# punchdriver.net
KiCad netlist of a schematic drawn in EAGLE
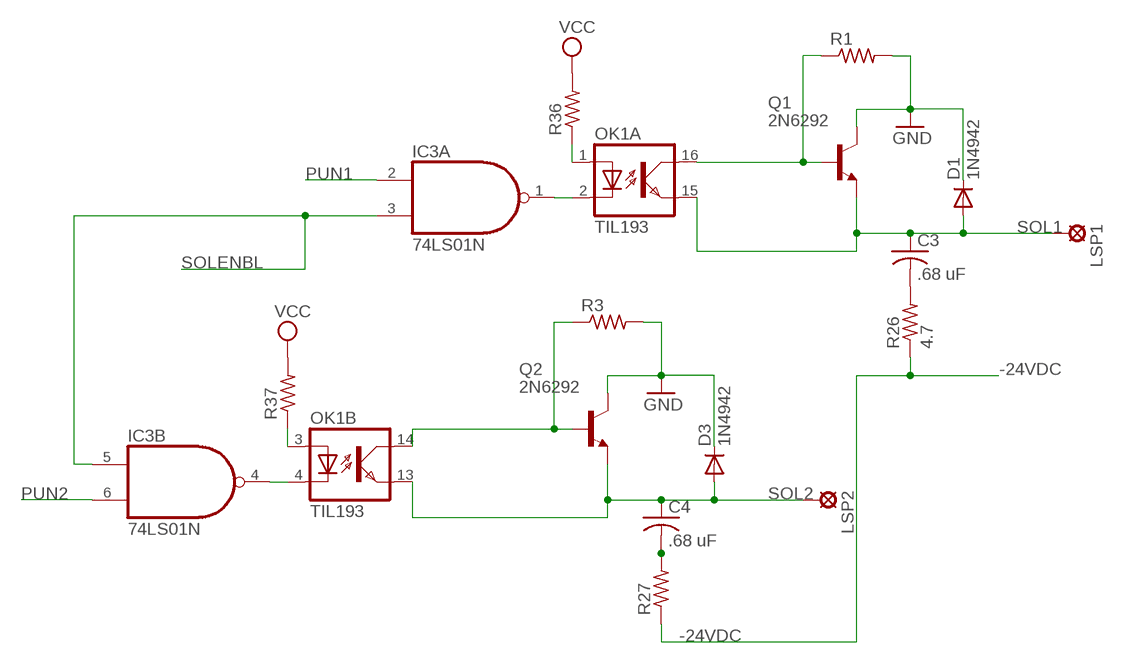
[diagram p0: schematic, sheet 1]
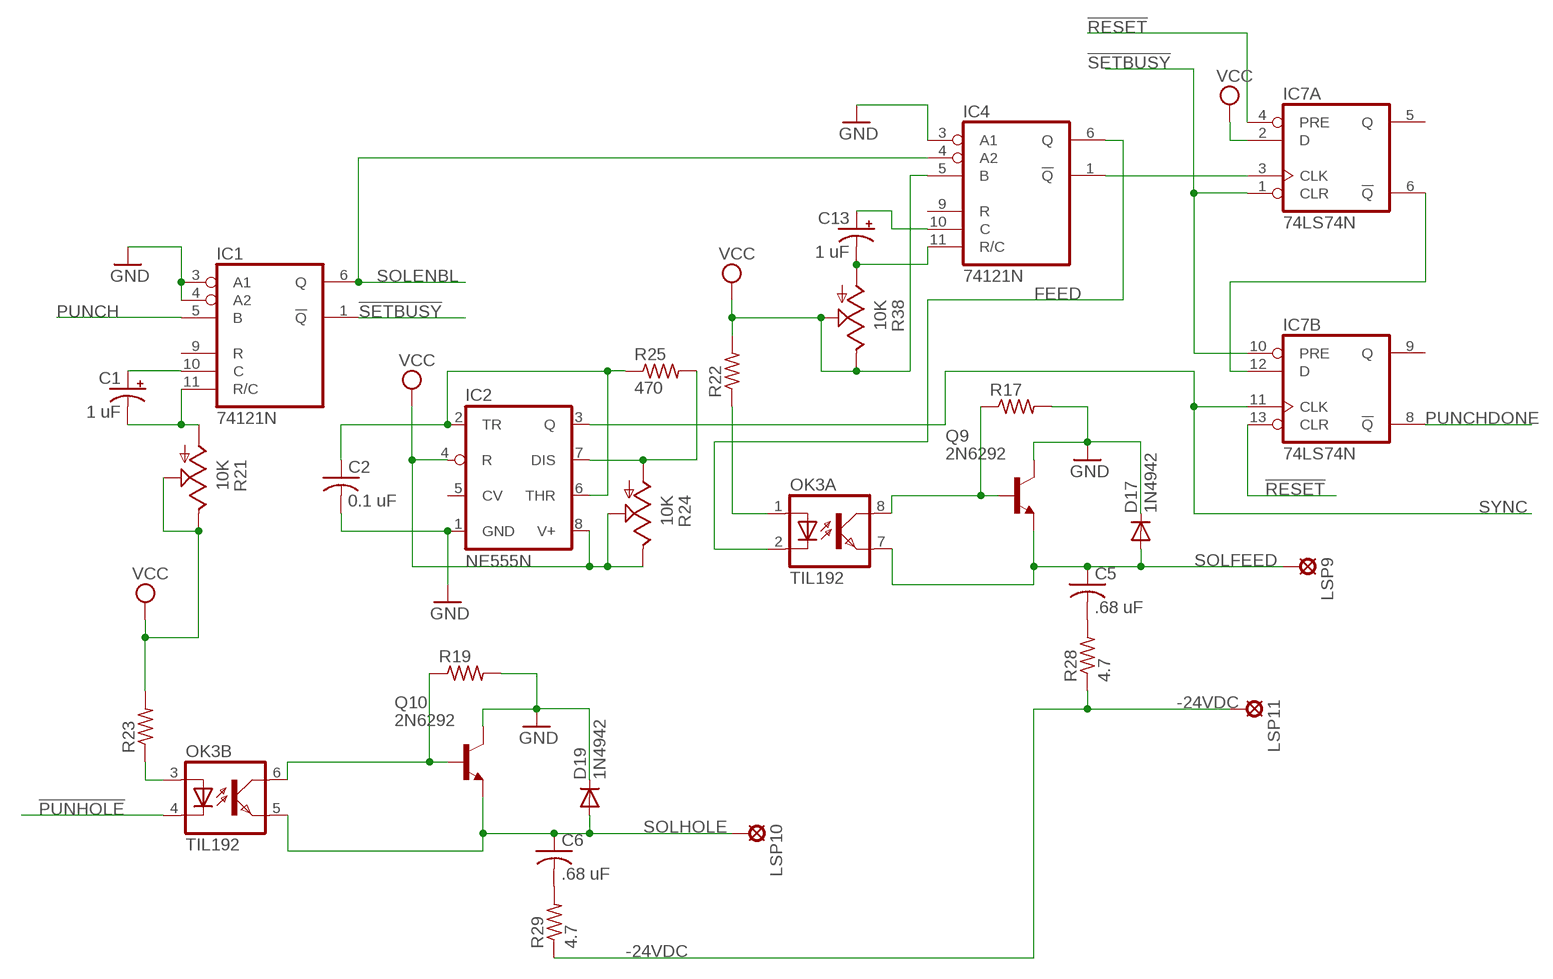
[diagram p1: schematic, sheet 2]
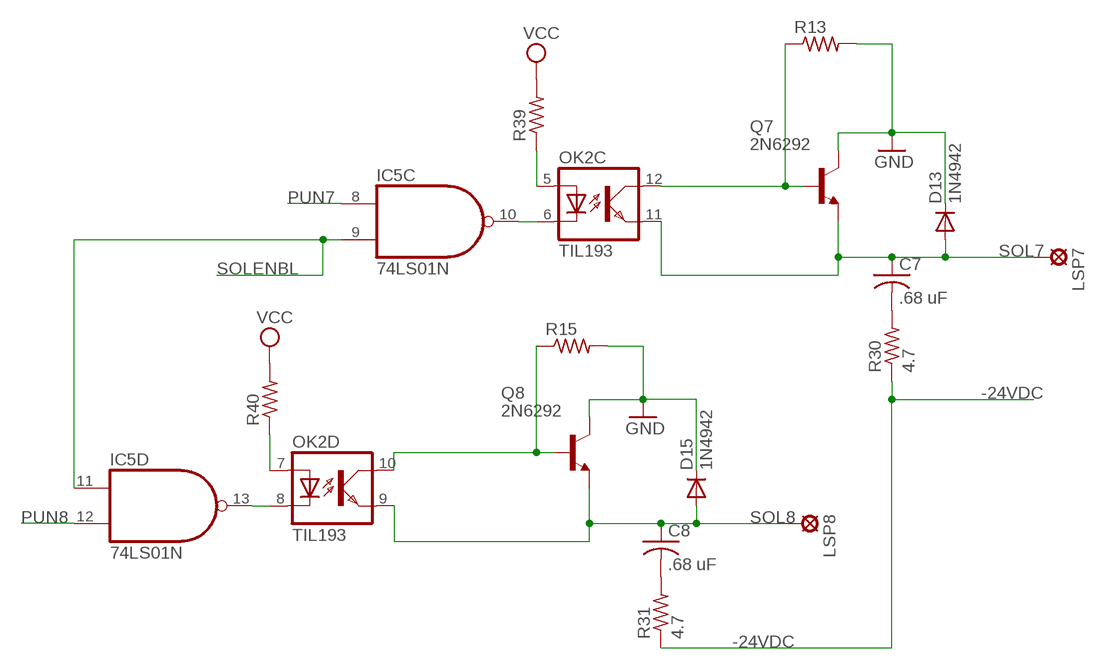
[diagram p2: schematic, sheet 3]
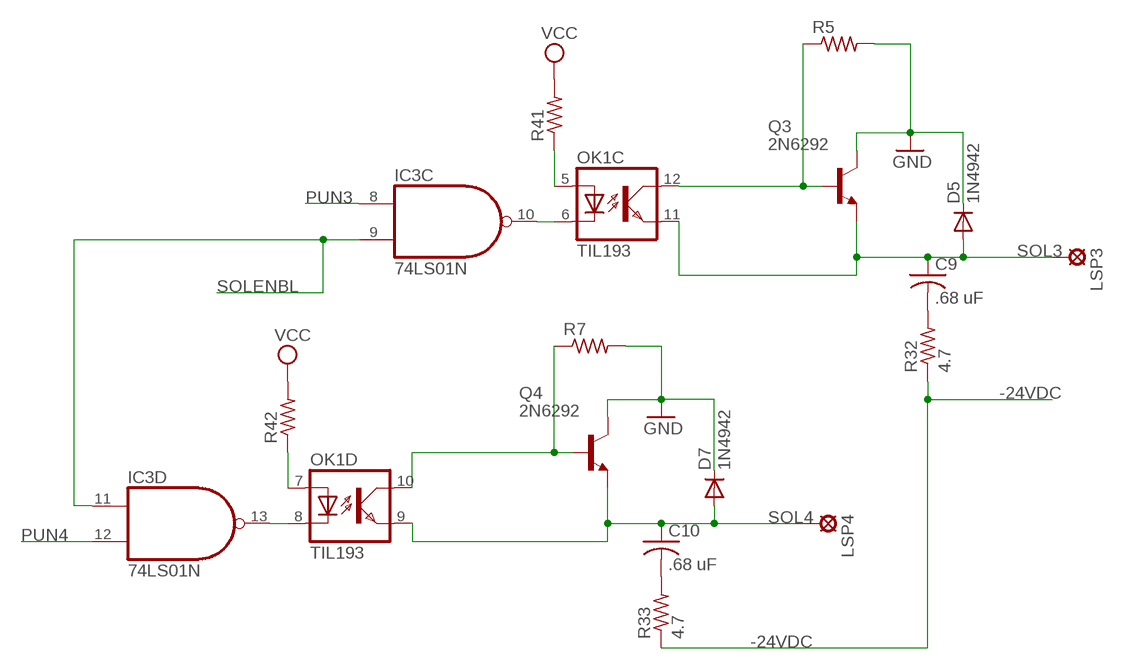
[diagram p3: schematic, sheet 4]
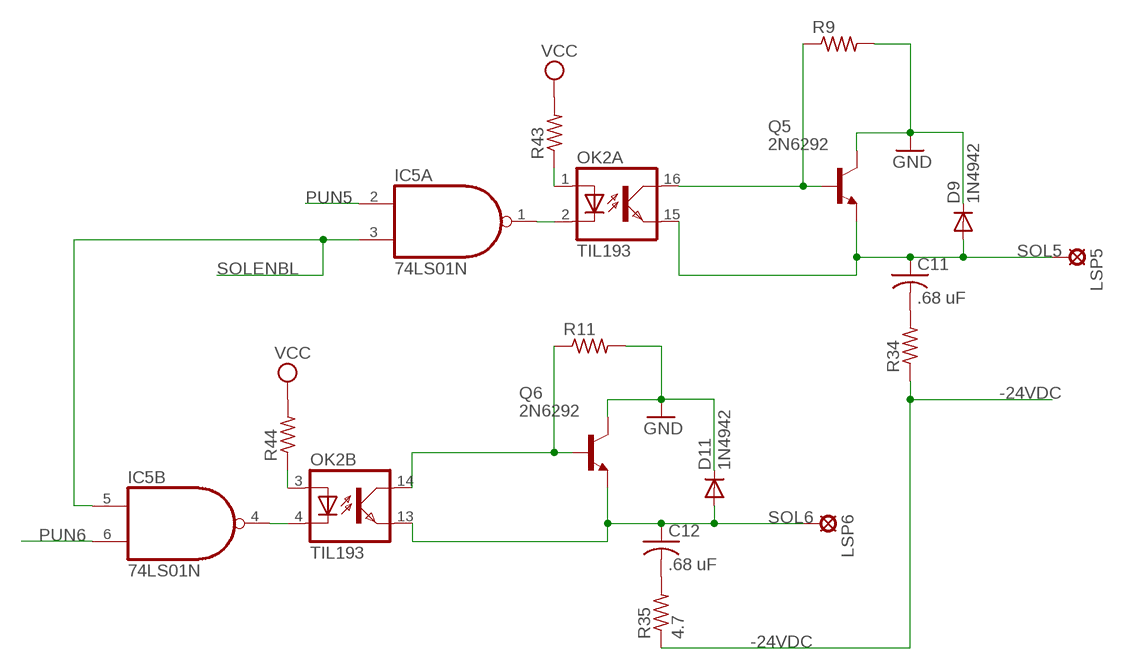
[diagram p4: schematic, sheet 5]
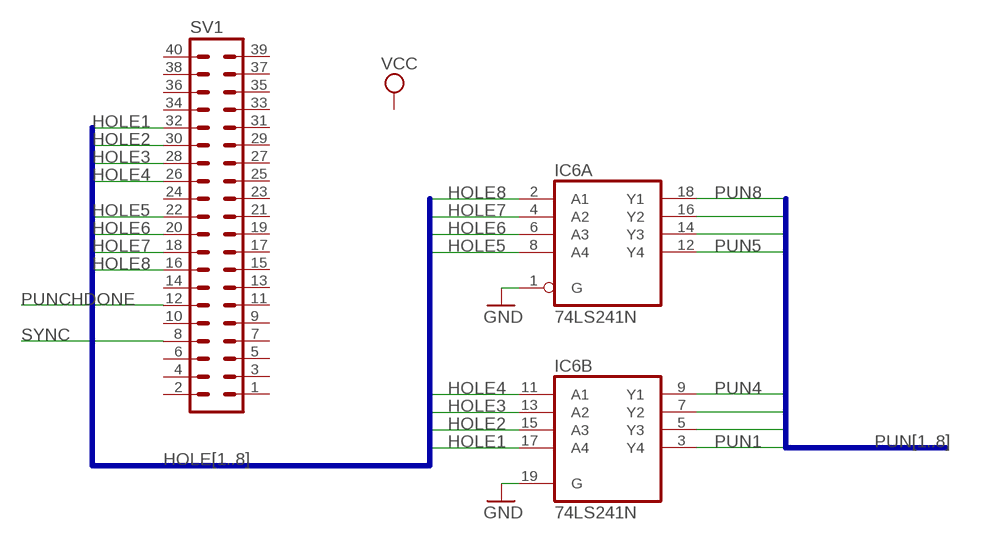
[diagram p5: schematic, sheet 6]

(export (version "E")
  (design (tool "Eeschema 10.0.6"))
  (components
    (comp (ref "IC6")
      (value "74LS241N")
      (footprint "eagle-import:DIL20")
      (libsource (lib "eagle-import") (part "74241NLS"))
    )
    (comp (ref "SV1")
      (value "MA20-2")
      (footprint "eagle-import:MA20-2")
      (libsource (lib "eagle-import") (part "MA20-2"))
    )
    (comp (ref "C1")
      (value "1 uF")
      (footprint "eagle-import:B45181A")
      (libsource (lib "eagle-import") (part "CPOL-USB45181A"))
    )
    (comp (ref "C2")
      (value "0.1 uF")
      (footprint "eagle-import:C050-025X075")
      (libsource (lib "eagle-import") (part "C-US050-025X075"))
    )
    (comp (ref "C5")
      (value ".68 uF")
      (footprint "eagle-import:C050-025X075")
      (libsource (lib "eagle-import") (part "C-US050-025X075"))
    )
    (comp (ref "C6")
      (value ".68 uF")
      (footprint "eagle-import:C050-025X075")
      (libsource (lib "eagle-import") (part "C-US050-025X075"))
    )
    (comp (ref "C13")
      (value "1 uF")
      (footprint "eagle-import:B45181A")
      (libsource (lib "eagle-import") (part "CPOL-USB45181A"))
    )
    (comp (ref "D17")
      (value "1N4942")
      (footprint "eagle-import:DO41-10")
      (libsource (lib "eagle-import") (part "1N4942"))
    )
    (comp (ref "D19")
      (value "1N4942")
      (footprint "eagle-import:DO41-10")
      (libsource (lib "eagle-import") (part "1N4942"))
    )
    (comp (ref "IC1")
      (value "74121N")
      (footprint "eagle-import:DIL14")
      (libsource (lib "eagle-import") (part "74121N"))
    )
    (comp (ref "IC2")
      (value "NE555N")
      (footprint "eagle-import:DIL08")
      (libsource (lib "eagle-import") (part "555NNE"))
    )
    (comp (ref "IC4")
      (value "74121N")
      (footprint "eagle-import:DIL14")
      (libsource (lib "eagle-import") (part "74121N"))
    )
    (comp (ref "IC7")
      (value "74LS74N")
      (footprint "eagle-import:DIL14")
      (libsource (lib "eagle-import") (part "7474NLS"))
    )
    (comp (ref "LSP9")
      (value "SE13")
      (footprint "eagle-import:SE13")
      (libsource (lib "eagle-import") (part "SE13"))
    )
    (comp (ref "LSP10")
      (value "SE13")
      (footprint "eagle-import:SE13")
      (libsource (lib "eagle-import") (part "SE13"))
    )
    (comp (ref "LSP11")
      (value "SE13")
      (footprint "eagle-import:SE13")
      (libsource (lib "eagle-import") (part "SE13"))
    )
    (comp (ref "OK3")
      (value "TIL192")
      (footprint "eagle-import:DIL08")
      (libsource (lib "eagle-import") (part "TIL192"))
    )
    (comp (ref "Q9")
      (value "2N6292")
      (footprint "eagle-import:TO220")
      (libsource (lib "eagle-import") (part "2N6292"))
    )
    (comp (ref "Q10")
      (value "2N6292")
      (footprint "eagle-import:TO220")
      (libsource (lib "eagle-import") (part "2N6292"))
    )
    (comp (ref "R17")
      (value "R-US_0207/10")
      (footprint "eagle-import:0207_10")
      (libsource (lib "eagle-import") (part "R-US_0207/10"))
    )
    (comp (ref "R19")
      (value "R-US_0207/10")
      (footprint "eagle-import:0207_10")
      (libsource (lib "eagle-import") (part "R-US_0207/10"))
    )
    (comp (ref "R21")
      (value "10K")
      (footprint "eagle-import:PT-SPIN")
      (libsource (lib "eagle-import") (part "TRIM_US-PTSPIN"))
    )
    (comp (ref "R22")
      (value "R-US_0207/10")
      (footprint "eagle-import:0207_10")
      (libsource (lib "eagle-import") (part "R-US_0207/10"))
    )
    (comp (ref "R23")
      (value "R-US_0207/10")
      (footprint "eagle-import:0207_10")
      (libsource (lib "eagle-import") (part "R-US_0207/10"))
    )
    (comp (ref "R24")
      (value "10K")
      (footprint "eagle-import:PT-SPIN")
      (libsource (lib "eagle-import") (part "TRIM_US-PTSPIN"))
    )
    (comp (ref "R25")
      (value "470")
      (footprint "eagle-import:0207_10")
      (libsource (lib "eagle-import") (part "R-US_0207/10"))
    )
    (comp (ref "R28")
      (value "4.7")
      (footprint "eagle-import:0207_10")
      (libsource (lib "eagle-import") (part "R-US_0207/10"))
    )
    (comp (ref "R29")
      (value "4.7")
      (footprint "eagle-import:0207_10")
      (libsource (lib "eagle-import") (part "R-US_0207/10"))
    )
    (comp (ref "R38")
      (value "10K")
      (footprint "eagle-import:PT-SPIN")
      (libsource (lib "eagle-import") (part "TRIM_US-PTSPIN"))
    )
    (comp (ref "C3")
      (value ".68 uF")
      (footprint "eagle-import:C050-025X075")
      (libsource (lib "eagle-import") (part "C-US050-025X075"))
    )
    (comp (ref "C4")
      (value ".68 uF")
      (footprint "eagle-import:C050-025X075")
      (libsource (lib "eagle-import") (part "C-US050-025X075"))
    )
    (comp (ref "D1")
      (value "1N4942")
      (footprint "eagle-import:DO41-10")
      (libsource (lib "eagle-import") (part "1N4942"))
    )
    (comp (ref "D3")
      (value "1N4942")
      (footprint "eagle-import:DO41-10")
      (libsource (lib "eagle-import") (part "1N4942"))
    )
    (comp (ref "IC3")
      (value "74LS01N")
      (footprint "eagle-import:DIL14")
      (libsource (lib "eagle-import") (part "7401NLS"))
    )
    (comp (ref "LSP1")
      (value "SE13")
      (footprint "eagle-import:SE13")
      (libsource (lib "eagle-import") (part "SE13"))
    )
    (comp (ref "LSP2")
      (value "SE13")
      (footprint "eagle-import:SE13")
      (libsource (lib "eagle-import") (part "SE13"))
    )
    (comp (ref "OK1")
      (value "TIL193")
      (footprint "eagle-import:DIL16")
      (libsource (lib "eagle-import") (part "TIL193"))
    )
    (comp (ref "Q1")
      (value "2N6292")
      (footprint "eagle-import:TO220")
      (libsource (lib "eagle-import") (part "2N6292"))
    )
    (comp (ref "Q2")
      (value "2N6292")
      (footprint "eagle-import:TO220")
      (libsource (lib "eagle-import") (part "2N6292"))
    )
    (comp (ref "R1")
      (value "R-US_0207/10")
      (footprint "eagle-import:0207_10")
      (libsource (lib "eagle-import") (part "R-US_0207/10"))
    )
    (comp (ref "R3")
      (value "R-US_0207/10")
      (footprint "eagle-import:0207_10")
      (libsource (lib "eagle-import") (part "R-US_0207/10"))
    )
    (comp (ref "R26")
      (value "4.7")
      (footprint "eagle-import:0207_10")
      (libsource (lib "eagle-import") (part "R-US_0207/10"))
    )
    (comp (ref "R27")
      (value "R-US_0207/10")
      (footprint "eagle-import:0207_10")
      (libsource (lib "eagle-import") (part "R-US_0207/10"))
    )
    (comp (ref "R36")
      (value "R-US_0207/10")
      (footprint "eagle-import:0207_10")
      (libsource (lib "eagle-import") (part "R-US_0207/10"))
    )
    (comp (ref "R37")
      (value "R-US_0207/10")
      (footprint "eagle-import:0207_10")
      (libsource (lib "eagle-import") (part "R-US_0207/10"))
    )
    (comp (ref "C7")
      (value ".68 uF")
      (footprint "eagle-import:C050-025X075")
      (libsource (lib "eagle-import") (part "C-US050-025X075"))
    )
    (comp (ref "C8")
      (value ".68 uF")
      (footprint "eagle-import:C050-025X075")
      (libsource (lib "eagle-import") (part "C-US050-025X075"))
    )
    (comp (ref "D13")
      (value "1N4942")
      (footprint "eagle-import:DO41-10")
      (libsource (lib "eagle-import") (part "1N4942"))
    )
    (comp (ref "D15")
      (value "1N4942")
      (footprint "eagle-import:DO41-10")
      (libsource (lib "eagle-import") (part "1N4942"))
    )
    (comp (ref "IC5")
      (value "74LS01N")
      (footprint "eagle-import:DIL14")
      (libsource (lib "eagle-import") (part "7401NLS"))
    )
    (comp (ref "LSP7")
      (value "SE13")
      (footprint "eagle-import:SE13")
      (libsource (lib "eagle-import") (part "SE13"))
    )
    (comp (ref "LSP8")
      (value "SE13")
      (footprint "eagle-import:SE13")
      (libsource (lib "eagle-import") (part "SE13"))
    )
    (comp (ref "OK2")
      (value "TIL193")
      (footprint "eagle-import:DIL16")
      (libsource (lib "eagle-import") (part "TIL193"))
    )
    (comp (ref "Q7")
      (value "2N6292")
      (footprint "eagle-import:TO220")
      (libsource (lib "eagle-import") (part "2N6292"))
    )
    (comp (ref "Q8")
      (value "2N6292")
      (footprint "eagle-import:TO220")
      (libsource (lib "eagle-import") (part "2N6292"))
    )
    (comp (ref "R13")
      (value "R-US_0207/10")
      (footprint "eagle-import:0207_10")
      (libsource (lib "eagle-import") (part "R-US_0207/10"))
    )
    (comp (ref "R15")
      (value "R-US_0207/10")
      (footprint "eagle-import:0207_10")
      (libsource (lib "eagle-import") (part "R-US_0207/10"))
    )
    (comp (ref "R30")
      (value "4.7")
      (footprint "eagle-import:0207_10")
      (libsource (lib "eagle-import") (part "R-US_0207/10"))
    )
    (comp (ref "R31")
      (value "4.7")
      (footprint "eagle-import:0207_10")
      (libsource (lib "eagle-import") (part "R-US_0207/10"))
    )
    (comp (ref "R39")
      (value "R-US_0207/10")
      (footprint "eagle-import:0207_10")
      (libsource (lib "eagle-import") (part "R-US_0207/10"))
    )
    (comp (ref "R40")
      (value "R-US_0207/10")
      (footprint "eagle-import:0207_10")
      (libsource (lib "eagle-import") (part "R-US_0207/10"))
    )
    (comp (ref "C9")
      (value ".68 uF")
      (footprint "eagle-import:C050-025X075")
      (libsource (lib "eagle-import") (part "C-US050-025X075"))
    )
    (comp (ref "C10")
      (value ".68 uF")
      (footprint "eagle-import:C050-025X075")
      (libsource (lib "eagle-import") (part "C-US050-025X075"))
    )
    (comp (ref "D5")
      (value "1N4942")
      (footprint "eagle-import:DO41-10")
      (libsource (lib "eagle-import") (part "1N4942"))
    )
    (comp (ref "D7")
      (value "1N4942")
      (footprint "eagle-import:DO41-10")
      (libsource (lib "eagle-import") (part "1N4942"))
    )
    (comp (ref "LSP3")
      (value "SE13")
      (footprint "eagle-import:SE13")
      (libsource (lib "eagle-import") (part "SE13"))
    )
    (comp (ref "LSP4")
      (value "SE13")
      (footprint "eagle-import:SE13")
      (libsource (lib "eagle-import") (part "SE13"))
    )
    (comp (ref "Q3")
      (value "2N6292")
      (footprint "eagle-import:TO220")
      (libsource (lib "eagle-import") (part "2N6292"))
    )
    (comp (ref "Q4")
      (value "2N6292")
      (footprint "eagle-import:TO220")
      (libsource (lib "eagle-import") (part "2N6292"))
    )
    (comp (ref "R5")
      (value "R-US_0207/10")
      (footprint "eagle-import:0207_10")
      (libsource (lib "eagle-import") (part "R-US_0207/10"))
    )
    (comp (ref "R7")
      (value "R-US_0207/10")
      (footprint "eagle-import:0207_10")
      (libsource (lib "eagle-import") (part "R-US_0207/10"))
    )
    (comp (ref "R32")
      (value "4.7")
      (footprint "eagle-import:0207_10")
      (libsource (lib "eagle-import") (part "R-US_0207/10"))
    )
    (comp (ref "R33")
      (value "4.7")
      (footprint "eagle-import:0207_10")
      (libsource (lib "eagle-import") (part "R-US_0207/10"))
    )
    (comp (ref "R41")
      (value "R-US_0207/10")
      (footprint "eagle-import:0207_10")
      (libsource (lib "eagle-import") (part "R-US_0207/10"))
    )
    (comp (ref "R42")
      (value "R-US_0207/10")
      (footprint "eagle-import:0207_10")
      (libsource (lib "eagle-import") (part "R-US_0207/10"))
    )
    (comp (ref "C11")
      (value ".68 uF")
      (footprint "eagle-import:C050-025X075")
      (libsource (lib "eagle-import") (part "C-US050-025X075"))
    )
    (comp (ref "C12")
      (value ".68 uF")
      (footprint "eagle-import:C050-025X075")
      (libsource (lib "eagle-import") (part "C-US050-025X075"))
    )
    (comp (ref "D9")
      (value "1N4942")
      (footprint "eagle-import:DO41-10")
      (libsource (lib "eagle-import") (part "1N4942"))
    )
    (comp (ref "D11")
      (value "1N4942")
      (footprint "eagle-import:DO41-10")
      (libsource (lib "eagle-import") (part "1N4942"))
    )
    (comp (ref "LSP5")
      (value "SE13")
      (footprint "eagle-import:SE13")
      (libsource (lib "eagle-import") (part "SE13"))
    )
    (comp (ref "LSP6")
      (value "SE13")
      (footprint "eagle-import:SE13")
      (libsource (lib "eagle-import") (part "SE13"))
    )
    (comp (ref "Q5")
      (value "2N6292")
      (footprint "eagle-import:TO220")
      (libsource (lib "eagle-import") (part "2N6292"))
    )
    (comp (ref "Q6")
      (value "2N6292")
      (footprint "eagle-import:TO220")
      (libsource (lib "eagle-import") (part "2N6292"))
    )
    (comp (ref "R9")
      (value "R-US_0207/10")
      (footprint "eagle-import:0207_10")
      (libsource (lib "eagle-import") (part "R-US_0207/10"))
    )
    (comp (ref "R11")
      (value "R-US_0207/10")
      (footprint "eagle-import:0207_10")
      (libsource (lib "eagle-import") (part "R-US_0207/10"))
    )
    (comp (ref "R34")
      (value "R-US_0207/10")
      (footprint "eagle-import:0207_10")
      (libsource (lib "eagle-import") (part "R-US_0207/10"))
    )
    (comp (ref "R35")
      (value "4.7")
      (footprint "eagle-import:0207_10")
      (libsource (lib "eagle-import") (part "R-US_0207/10"))
    )
    (comp (ref "R43")
      (value "R-US_0207/10")
      (footprint "eagle-import:0207_10")
      (libsource (lib "eagle-import") (part "R-US_0207/10"))
    )
    (comp (ref "R44")
      (value "R-US_0207/10")
      (footprint "eagle-import:0207_10")
      (libsource (lib "eagle-import") (part "R-US_0207/10"))
    )
  )
  (nets
    (net (code "1") (name "-24VDC") (class "Default")
      (node (ref "LSP11") (pin "MP") (pinfunction "MP_MP") (pintype "passive"))
      (node (ref "R26") (pin "1") (pinfunction "1_1") (pintype "passive"))
      (node (ref "R27") (pin "1") (pinfunction "1_1") (pintype "passive"))
      (node (ref "R28") (pin "1") (pinfunction "1_1") (pintype "passive"))
      (node (ref "R29") (pin "1") (pinfunction "1_1") (pintype "passive"))
      (node (ref "R30") (pin "1") (pinfunction "1_1") (pintype "passive"))
      (node (ref "R31") (pin "1") (pinfunction "1_1") (pintype "passive"))
      (node (ref "R32") (pin "1") (pinfunction "1_1") (pintype "passive"))
      (node (ref "R33") (pin "1") (pinfunction "1_1") (pintype "passive"))
      (node (ref "R34") (pin "1") (pinfunction "1_1") (pintype "passive"))
      (node (ref "R35") (pin "1") (pinfunction "1_1") (pintype "passive"))
    )
    (net (code "4") (name "FEED") (class "Default")
      (node (ref "IC4") (pin "6") (pinfunction "Q_6") (pintype "output"))
      (node (ref "OK3") (pin "2") (pinfunction "C_2") (pintype "passive"))
    )
    (net (code "5") (name "GND") (class "Default")
      (node (ref "C2") (pin "2") (pinfunction "2_2") (pintype "passive"))
      (node (ref "D1") (pin "C") (pinfunction "C_C") (pintype "passive"))
      (node (ref "D11") (pin "C") (pinfunction "C_C") (pintype "passive"))
      (node (ref "D13") (pin "C") (pinfunction "C_C") (pintype "passive"))
      (node (ref "D15") (pin "C") (pinfunction "C_C") (pintype "passive"))
      (node (ref "D17") (pin "C") (pinfunction "C_C") (pintype "passive"))
      (node (ref "D19") (pin "C") (pinfunction "C_C") (pintype "passive"))
      (node (ref "D3") (pin "C") (pinfunction "C_C") (pintype "passive"))
      (node (ref "D5") (pin "C") (pinfunction "C_C") (pintype "passive"))
      (node (ref "D7") (pin "C") (pinfunction "C_C") (pintype "passive"))
      (node (ref "D9") (pin "C") (pinfunction "C_C") (pintype "passive"))
      (node (ref "IC1") (pin "3") (pinfunction "A1_3") (pintype "input"))
      (node (ref "IC1") (pin "4") (pinfunction "A2_4") (pintype "input"))
      (node (ref "IC2") (pin "1") (pinfunction "GND_1") (pintype "power_in"))
      (node (ref "IC4") (pin "3") (pinfunction "A1_3") (pintype "input"))
      (node (ref "IC6") (pin "1") (pinfunction "G_1") (pintype "input"))
      (node (ref "IC6") (pin "19") (pinfunction "G_19") (pintype "input"))
      (node (ref "Q1") (pin "2") (pinfunction "C_2") (pintype "passive"))
      (node (ref "Q10") (pin "2") (pinfunction "C_2") (pintype "passive"))
      (node (ref "Q2") (pin "2") (pinfunction "C_2") (pintype "passive"))
      (node (ref "Q3") (pin "2") (pinfunction "C_2") (pintype "passive"))
      (node (ref "Q4") (pin "2") (pinfunction "C_2") (pintype "passive"))
      (node (ref "Q5") (pin "2") (pinfunction "C_2") (pintype "passive"))
      (node (ref "Q6") (pin "2") (pinfunction "C_2") (pintype "passive"))
      (node (ref "Q7") (pin "2") (pinfunction "C_2") (pintype "passive"))
      (node (ref "Q8") (pin "2") (pinfunction "C_2") (pintype "passive"))
      (node (ref "Q9") (pin "2") (pinfunction "C_2") (pintype "passive"))
      (node (ref "R1") (pin "2") (pinfunction "2_2") (pintype "passive"))
      (node (ref "R11") (pin "2") (pinfunction "2_2") (pintype "passive"))
      (node (ref "R13") (pin "2") (pinfunction "2_2") (pintype "passive"))
      (node (ref "R15") (pin "2") (pinfunction "2_2") (pintype "passive"))
      (node (ref "R17") (pin "2") (pinfunction "2_2") (pintype "passive"))
      (node (ref "R19") (pin "2") (pinfunction "2_2") (pintype "passive"))
      (node (ref "R3") (pin "2") (pinfunction "2_2") (pintype "passive"))
      (node (ref "R5") (pin "2") (pinfunction "2_2") (pintype "passive"))
      (node (ref "R7") (pin "2") (pinfunction "2_2") (pintype "passive"))
      (node (ref "R9") (pin "2") (pinfunction "2_2") (pintype "passive"))
    )
    (net (code "6") (name "HOLE1") (class "Default")
      (node (ref "IC6") (pin "17") (pinfunction "A4_17") (pintype "input"))
      (node (ref "SV1") (pin "32") (pinfunction "32_32") (pintype "passive"))
    )
    (net (code "7") (name "HOLE2") (class "Default")
      (node (ref "IC6") (pin "15") (pinfunction "A3_15") (pintype "input"))
      (node (ref "SV1") (pin "30") (pinfunction "30_30") (pintype "passive"))
    )
    (net (code "8") (name "HOLE3") (class "Default")
      (node (ref "IC6") (pin "13") (pinfunction "A2_13") (pintype "input"))
      (node (ref "SV1") (pin "28") (pinfunction "28_28") (pintype "passive"))
    )
    (net (code "9") (name "HOLE4") (class "Default")
      (node (ref "IC6") (pin "11") (pinfunction "A1_11") (pintype "input"))
      (node (ref "SV1") (pin "26") (pinfunction "26_26") (pintype "passive"))
    )
    (net (code "10") (name "HOLE5") (class "Default")
      (node (ref "IC6") (pin "8") (pinfunction "A4_8") (pintype "input"))
      (node (ref "SV1") (pin "22") (pinfunction "22_22") (pintype "passive"))
    )
    (net (code "11") (name "HOLE6") (class "Default")
      (node (ref "IC6") (pin "6") (pinfunction "A3_6") (pintype "input"))
      (node (ref "SV1") (pin "20") (pinfunction "20_20") (pintype "passive"))
    )
    (net (code "12") (name "HOLE7") (class "Default")
      (node (ref "IC6") (pin "4") (pinfunction "A2_4") (pintype "input"))
      (node (ref "SV1") (pin "18") (pinfunction "18_18") (pintype "passive"))
    )
    (net (code "13") (name "HOLE8") (class "Default")
      (node (ref "IC6") (pin "2") (pinfunction "A1_2") (pintype "input"))
      (node (ref "SV1") (pin "16") (pinfunction "16_16") (pintype "passive"))
    )
    (net (code "14") (name "Net-(C3-Pad2)") (class "Default")
      (node (ref "C3") (pin "2") (pinfunction "2_2") (pintype "passive"))
      (node (ref "R26") (pin "2") (pinfunction "2_2") (pintype "passive"))
    )
    (net (code "15") (name "Net-(C4-Pad2)") (class "Default")
      (node (ref "C4") (pin "2") (pinfunction "2_2") (pintype "passive"))
      (node (ref "R27") (pin "2") (pinfunction "2_2") (pintype "passive"))
    )
    (net (code "16") (name "Net-(C5-Pad2)") (class "Default")
      (node (ref "C5") (pin "2") (pinfunction "2_2") (pintype "passive"))
      (node (ref "R28") (pin "2") (pinfunction "2_2") (pintype "passive"))
    )
    (net (code "17") (name "Net-(C6-Pad2)") (class "Default")
      (node (ref "C6") (pin "2") (pinfunction "2_2") (pintype "passive"))
      (node (ref "R29") (pin "2") (pinfunction "2_2") (pintype "passive"))
    )
    (net (code "18") (name "Net-(C7-Pad2)") (class "Default")
      (node (ref "C7") (pin "2") (pinfunction "2_2") (pintype "passive"))
      (node (ref "R30") (pin "2") (pinfunction "2_2") (pintype "passive"))
    )
    (net (code "19") (name "Net-(C8-Pad2)") (class "Default")
      (node (ref "C8") (pin "2") (pinfunction "2_2") (pintype "passive"))
      (node (ref "R31") (pin "2") (pinfunction "2_2") (pintype "passive"))
    )
    (net (code "20") (name "Net-(C9-Pad2)") (class "Default")
      (node (ref "C9") (pin "2") (pinfunction "2_2") (pintype "passive"))
      (node (ref "R32") (pin "2") (pinfunction "2_2") (pintype "passive"))
    )
    (net (code "21") (name "Net-(C10-Pad2)") (class "Default")
      (node (ref "C10") (pin "2") (pinfunction "2_2") (pintype "passive"))
      (node (ref "R33") (pin "2") (pinfunction "2_2") (pintype "passive"))
    )
    (net (code "22") (name "Net-(C11-Pad2)") (class "Default")
      (node (ref "C11") (pin "2") (pinfunction "2_2") (pintype "passive"))
      (node (ref "R34") (pin "2") (pinfunction "2_2") (pintype "passive"))
    )
    (net (code "23") (name "Net-(C12-Pad2)") (class "Default")
      (node (ref "C12") (pin "2") (pinfunction "2_2") (pintype "passive"))
      (node (ref "R35") (pin "2") (pinfunction "2_2") (pintype "passive"))
    )
    (net (code "24") (name "Net-(IC1A-C)") (class "Default")
      (node (ref "C1") (pin "+") (pinfunction "+_+") (pintype "passive"))
      (node (ref "IC1") (pin "10") (pinfunction "C_10") (pintype "input"))
    )
    (net (code "25") (name "Net-(IC1A-R{slash}C)") (class "Default")
      (node (ref "C1") (pin "-") (pinfunction "-_-") (pintype "passive"))
      (node (ref "IC1") (pin "11") (pinfunction "R/C_11") (pintype "input"))
      (node (ref "R21") (pin "A") (pinfunction "A_A") (pintype "passive"))
    )
    (net (code "26") (name "Net-(IC2-DIS)") (class "Default")
      (node (ref "IC2") (pin "7") (pinfunction "DIS_7") (pintype "input"))
      (node (ref "R24") (pin "A") (pinfunction "A_A") (pintype "passive"))
      (node (ref "R25") (pin "2") (pinfunction "2_2") (pintype "passive"))
    )
    (net (code "27") (name "Net-(IC2-THR)") (class "Default")
      (node (ref "C2") (pin "1") (pinfunction "1_1") (pintype "passive"))
      (node (ref "IC2") (pin "2") (pinfunction "TR_2") (pintype "input"))
      (node (ref "IC2") (pin "6") (pinfunction "THR_6") (pintype "input"))
      (node (ref "R25") (pin "1") (pinfunction "1_1") (pintype "passive"))
    )
    (net (code "28") (name "Net-(IC3A-O)") (class "Default")
      (node (ref "IC3") (pin "1") (pinfunction "O_1") (pintype "open_collector"))
      (node (ref "OK1") (pin "2") (pinfunction "C_2") (pintype "passive"))
    )
    (net (code "29") (name "Net-(IC3B-O)") (class "Default")
      (node (ref "IC3") (pin "4") (pinfunction "O_4") (pintype "open_collector"))
      (node (ref "OK1") (pin "4") (pinfunction "C_4") (pintype "passive"))
    )
    (net (code "30") (name "Net-(IC3C-O)") (class "Default")
      (node (ref "IC3") (pin "10") (pinfunction "O_10") (pintype "open_collector"))
      (node (ref "OK1") (pin "6") (pinfunction "C_6") (pintype "passive"))
    )
    (net (code "31") (name "Net-(IC3D-O)") (class "Default")
      (node (ref "IC3") (pin "13") (pinfunction "O_13") (pintype "open_collector"))
      (node (ref "OK1") (pin "8") (pinfunction "C_8") (pintype "passive"))
    )
    (net (code "32") (name "Net-(IC4A-C)") (class "Default")
      (node (ref "C13") (pin "+") (pinfunction "+_+") (pintype "passive"))
      (node (ref "IC4") (pin "10") (pinfunction "C_10") (pintype "input"))
    )
    (net (code "33") (name "Net-(IC4A-R{slash}C)") (class "Default")
      (node (ref "C13") (pin "-") (pinfunction "-_-") (pintype "passive"))
      (node (ref "IC4") (pin "11") (pinfunction "R/C_11") (pintype "input"))
      (node (ref "R38") (pin "A") (pinfunction "A_A") (pintype "passive"))
    )
    (net (code "34") (name "Net-(IC4A-~{Q})") (class "Default")
      (node (ref "IC4") (pin "1") (pinfunction "~{Q}_1") (pintype "output"))
      (node (ref "IC7") (pin "3") (pinfunction "CLK_3") (pintype "input"))
    )
    (net (code "35") (name "Net-(IC5A-O)") (class "Default")
      (node (ref "IC5") (pin "1") (pinfunction "O_1") (pintype "open_collector"))
      (node (ref "OK2") (pin "2") (pinfunction "C_2") (pintype "passive"))
    )
    (net (code "36") (name "Net-(IC5B-O)") (class "Default")
      (node (ref "IC5") (pin "4") (pinfunction "O_4") (pintype "open_collector"))
      (node (ref "OK2") (pin "4") (pinfunction "C_4") (pintype "passive"))
    )
    (net (code "37") (name "Net-(IC5C-O)") (class "Default")
      (node (ref "IC5") (pin "10") (pinfunction "O_10") (pintype "open_collector"))
      (node (ref "OK2") (pin "6") (pinfunction "C_6") (pintype "passive"))
    )
    (net (code "38") (name "Net-(IC5D-O)") (class "Default")
      (node (ref "IC5") (pin "13") (pinfunction "O_13") (pintype "open_collector"))
      (node (ref "OK2") (pin "8") (pinfunction "C_8") (pintype "passive"))
    )
    (net (code "39") (name "Net-(IC7A-~{Q})") (class "Default")
      (node (ref "IC7") (pin "12") (pinfunction "D_12") (pintype "input"))
      (node (ref "IC7") (pin "6") (pinfunction "~{Q}_6") (pintype "output"))
    )
    (net (code "40") (name "Net-(OK1A-A)") (class "Default")
      (node (ref "OK1") (pin "1") (pinfunction "A_1") (pintype "passive"))
      (node (ref "R36") (pin "1") (pinfunction "1_1") (pintype "passive"))
    )
    (net (code "41") (name "Net-(OK1A-COL)") (class "Default")
      (node (ref "OK1") (pin "16") (pinfunction "COL_16") (pintype "passive"))
      (node (ref "Q1") (pin "1") (pinfunction "B_1") (pintype "passive"))
      (node (ref "R1") (pin "1") (pinfunction "1_1") (pintype "passive"))
    )
    (net (code "42") (name "Net-(OK1B-A)") (class "Default")
      (node (ref "OK1") (pin "3") (pinfunction "A_3") (pintype "passive"))
      (node (ref "R37") (pin "1") (pinfunction "1_1") (pintype "passive"))
    )
    (net (code "43") (name "Net-(OK1B-COL)") (class "Default")
      (node (ref "OK1") (pin "14") (pinfunction "COL_14") (pintype "passive"))
      (node (ref "Q2") (pin "1") (pinfunction "B_1") (pintype "passive"))
      (node (ref "R3") (pin "1") (pinfunction "1_1") (pintype "passive"))
    )
    (net (code "44") (name "Net-(OK1C-A)") (class "Default")
      (node (ref "OK1") (pin "5") (pinfunction "A_5") (pintype "passive"))
      (node (ref "R41") (pin "1") (pinfunction "1_1") (pintype "passive"))
    )
    (net (code "45") (name "Net-(OK1C-COL)") (class "Default")
      (node (ref "OK1") (pin "12") (pinfunction "COL_12") (pintype "passive"))
      (node (ref "Q3") (pin "1") (pinfunction "B_1") (pintype "passive"))
      (node (ref "R5") (pin "1") (pinfunction "1_1") (pintype "passive"))
    )
    (net (code "46") (name "Net-(OK1D-A)") (class "Default")
      (node (ref "OK1") (pin "7") (pinfunction "A_7") (pintype "passive"))
      (node (ref "R42") (pin "1") (pinfunction "1_1") (pintype "passive"))
    )
    (net (code "47") (name "Net-(OK1D-COL)") (class "Default")
      (node (ref "OK1") (pin "10") (pinfunction "COL_10") (pintype "passive"))
      (node (ref "Q4") (pin "1") (pinfunction "B_1") (pintype "passive"))
      (node (ref "R7") (pin "1") (pinfunction "1_1") (pintype "passive"))
    )
    (net (code "48") (name "Net-(OK2A-A)") (class "Default")
      (node (ref "OK2") (pin "1") (pinfunction "A_1") (pintype "passive"))
      (node (ref "R43") (pin "1") (pinfunction "1_1") (pintype "passive"))
    )
    (net (code "49") (name "Net-(OK2A-COL)") (class "Default")
      (node (ref "OK2") (pin "16") (pinfunction "COL_16") (pintype "passive"))
      (node (ref "Q5") (pin "1") (pinfunction "B_1") (pintype "passive"))
      (node (ref "R9") (pin "1") (pinfunction "1_1") (pintype "passive"))
    )
    (net (code "50") (name "Net-(OK2B-A)") (class "Default")
      (node (ref "OK2") (pin "3") (pinfunction "A_3") (pintype "passive"))
      (node (ref "R44") (pin "1") (pinfunction "1_1") (pintype "passive"))
    )
    (net (code "51") (name "Net-(OK2B-COL)") (class "Default")
      (node (ref "OK2") (pin "14") (pinfunction "COL_14") (pintype "passive"))
      (node (ref "Q6") (pin "1") (pinfunction "B_1") (pintype "passive"))
      (node (ref "R11") (pin "1") (pinfunction "1_1") (pintype "passive"))
    )
    (net (code "52") (name "Net-(OK2C-A)") (class "Default")
      (node (ref "OK2") (pin "5") (pinfunction "A_5") (pintype "passive"))
      (node (ref "R39") (pin "1") (pinfunction "1_1") (pintype "passive"))
    )
    (net (code "53") (name "Net-(OK2C-COL)") (class "Default")
      (node (ref "OK2") (pin "12") (pinfunction "COL_12") (pintype "passive"))
      (node (ref "Q7") (pin "1") (pinfunction "B_1") (pintype "passive"))
      (node (ref "R13") (pin "1") (pinfunction "1_1") (pintype "passive"))
    )
    (net (code "54") (name "Net-(OK2D-A)") (class "Default")
      (node (ref "OK2") (pin "7") (pinfunction "A_7") (pintype "passive"))
      (node (ref "R40") (pin "1") (pinfunction "1_1") (pintype "passive"))
    )
    (net (code "55") (name "Net-(OK2D-COL)") (class "Default")
      (node (ref "OK2") (pin "10") (pinfunction "COL_10") (pintype "passive"))
      (node (ref "Q8") (pin "1") (pinfunction "B_1") (pintype "passive"))
      (node (ref "R15") (pin "1") (pinfunction "1_1") (pintype "passive"))
    )
    (net (code "56") (name "Net-(OK3A-A)") (class "Default")
      (node (ref "OK3") (pin "1") (pinfunction "A_1") (pintype "passive"))
      (node (ref "R22") (pin "1") (pinfunction "1_1") (pintype "passive"))
    )
    (net (code "57") (name "Net-(OK3A-COL)") (class "Default")
      (node (ref "OK3") (pin "8") (pinfunction "COL_8") (pintype "passive"))
      (node (ref "Q9") (pin "1") (pinfunction "B_1") (pintype "passive"))
      (node (ref "R17") (pin "1") (pinfunction "1_1") (pintype "passive"))
    )
    (net (code "58") (name "Net-(OK3B-A)") (class "Default")
      (node (ref "OK3") (pin "3") (pinfunction "A_3") (pintype "passive"))
      (node (ref "R23") (pin "1") (pinfunction "1_1") (pintype "passive"))
    )
    (net (code "59") (name "Net-(OK3B-COL)") (class "Default")
      (node (ref "OK3") (pin "6") (pinfunction "COL_6") (pintype "passive"))
      (node (ref "Q10") (pin "1") (pinfunction "B_1") (pintype "passive"))
      (node (ref "R19") (pin "1") (pinfunction "1_1") (pintype "passive"))
    )
    (net (code "60") (name "PUN1") (class "Default")
      (node (ref "IC3") (pin "2") (pinfunction "I0_2") (pintype "input"))
      (node (ref "IC6") (pin "3") (pinfunction "Y4_3") (pintype "tri_state"))
    )
    (net (code "61") (name "PUN2") (class "Default")
      (node (ref "IC3") (pin "6") (pinfunction "I1_6") (pintype "input"))
      (node (ref "IC6") (pin "5") (pinfunction "Y3_5") (pintype "tri_state"))
    )
    (net (code "62") (name "PUN3") (class "Default")
      (node (ref "IC3") (pin "8") (pinfunction "I0_8") (pintype "input"))
      (node (ref "IC6") (pin "7") (pinfunction "Y2_7") (pintype "tri_state"))
    )
    (net (code "63") (name "PUN4") (class "Default")
      (node (ref "IC3") (pin "12") (pinfunction "I1_12") (pintype "input"))
      (node (ref "IC6") (pin "9") (pinfunction "Y1_9") (pintype "tri_state"))
    )
    (net (code "64") (name "PUN5") (class "Default")
      (node (ref "IC5") (pin "2") (pinfunction "I0_2") (pintype "input"))
      (node (ref "IC6") (pin "12") (pinfunction "Y4_12") (pintype "tri_state"))
    )
    (net (code "65") (name "PUN6") (class "Default")
      (node (ref "IC5") (pin "6") (pinfunction "I1_6") (pintype "input"))
      (node (ref "IC6") (pin "14") (pinfunction "Y3_14") (pintype "tri_state"))
    )
    (net (code "66") (name "PUN7") (class "Default")
      (node (ref "IC5") (pin "8") (pinfunction "I0_8") (pintype "input"))
      (node (ref "IC6") (pin "16") (pinfunction "Y2_16") (pintype "tri_state"))
    )
    (net (code "67") (name "PUN8") (class "Default")
      (node (ref "IC5") (pin "12") (pinfunction "I1_12") (pintype "input"))
      (node (ref "IC6") (pin "18") (pinfunction "Y1_18") (pintype "tri_state"))
    )
    (net (code "68") (name "PUNCH") (class "Default")
      (node (ref "IC1") (pin "5") (pinfunction "B_5") (pintype "input"))
    )
    (net (code "69") (name "PUNCHDONE") (class "Default")
      (node (ref "IC7") (pin "8") (pinfunction "~{Q}_8") (pintype "output"))
      (node (ref "SV1") (pin "12") (pinfunction "12_12") (pintype "passive"))
    )
    (net (code "70") (name "SOL1") (class "Default")
      (node (ref "C3") (pin "1") (pinfunction "1_1") (pintype "passive"))
      (node (ref "D1") (pin "A") (pinfunction "A_A") (pintype "passive"))
      (node (ref "LSP1") (pin "MP") (pinfunction "MP_MP") (pintype "passive"))
      (node (ref "OK1") (pin "15") (pinfunction "EMIT_15") (pintype "passive"))
      (node (ref "Q1") (pin "3") (pinfunction "E_3") (pintype "passive"))
    )
    (net (code "71") (name "SOL2") (class "Default")
      (node (ref "C4") (pin "1") (pinfunction "1_1") (pintype "passive"))
      (node (ref "D3") (pin "A") (pinfunction "A_A") (pintype "passive"))
      (node (ref "LSP2") (pin "MP") (pinfunction "MP_MP") (pintype "passive"))
      (node (ref "OK1") (pin "13") (pinfunction "EMIT_13") (pintype "passive"))
      (node (ref "Q2") (pin "3") (pinfunction "E_3") (pintype "passive"))
    )
    (net (code "72") (name "SOL3") (class "Default")
      (node (ref "C9") (pin "1") (pinfunction "1_1") (pintype "passive"))
      (node (ref "D5") (pin "A") (pinfunction "A_A") (pintype "passive"))
      (node (ref "LSP3") (pin "MP") (pinfunction "MP_MP") (pintype "passive"))
      (node (ref "OK1") (pin "11") (pinfunction "EMIT_11") (pintype "passive"))
      (node (ref "Q3") (pin "3") (pinfunction "E_3") (pintype "passive"))
    )
    (net (code "73") (name "SOL4") (class "Default")
      (node (ref "C10") (pin "1") (pinfunction "1_1") (pintype "passive"))
      (node (ref "D7") (pin "A") (pinfunction "A_A") (pintype "passive"))
      (node (ref "LSP4") (pin "MP") (pinfunction "MP_MP") (pintype "passive"))
      (node (ref "OK1") (pin "9") (pinfunction "EMIT_9") (pintype "passive"))
      (node (ref "Q4") (pin "3") (pinfunction "E_3") (pintype "passive"))
    )
    (net (code "74") (name "SOL5") (class "Default")
      (node (ref "C11") (pin "1") (pinfunction "1_1") (pintype "passive"))
      (node (ref "D9") (pin "A") (pinfunction "A_A") (pintype "passive"))
      (node (ref "LSP5") (pin "MP") (pinfunction "MP_MP") (pintype "passive"))
      (node (ref "OK2") (pin "15") (pinfunction "EMIT_15") (pintype "passive"))
      (node (ref "Q5") (pin "3") (pinfunction "E_3") (pintype "passive"))
    )
    (net (code "75") (name "SOL6") (class "Default")
      (node (ref "C12") (pin "1") (pinfunction "1_1") (pintype "passive"))
      (node (ref "D11") (pin "A") (pinfunction "A_A") (pintype "passive"))
      (node (ref "LSP6") (pin "MP") (pinfunction "MP_MP") (pintype "passive"))
      (node (ref "OK2") (pin "13") (pinfunction "EMIT_13") (pintype "passive"))
      (node (ref "Q6") (pin "3") (pinfunction "E_3") (pintype "passive"))
    )
    (net (code "76") (name "SOL7") (class "Default")
      (node (ref "C7") (pin "1") (pinfunction "1_1") (pintype "passive"))
      (node (ref "D13") (pin "A") (pinfunction "A_A") (pintype "passive"))
      (node (ref "LSP7") (pin "MP") (pinfunction "MP_MP") (pintype "passive"))
      (node (ref "OK2") (pin "11") (pinfunction "EMIT_11") (pintype "passive"))
      (node (ref "Q7") (pin "3") (pinfunction "E_3") (pintype "passive"))
    )
    (net (code "77") (name "SOL8") (class "Default")
      (node (ref "C8") (pin "1") (pinfunction "1_1") (pintype "passive"))
      (node (ref "D15") (pin "A") (pinfunction "A_A") (pintype "passive"))
      (node (ref "LSP8") (pin "MP") (pinfunction "MP_MP") (pintype "passive"))
      (node (ref "OK2") (pin "9") (pinfunction "EMIT_9") (pintype "passive"))
      (node (ref "Q8") (pin "3") (pinfunction "E_3") (pintype "passive"))
    )
    (net (code "78") (name "SOLENBL") (class "Default")
      (node (ref "IC1") (pin "6") (pinfunction "Q_6") (pintype "output"))
      (node (ref "IC3") (pin "11") (pinfunction "I0_11") (pintype "input"))
      (node (ref "IC3") (pin "3") (pinfunction "I1_3") (pintype "input"))
      (node (ref "IC3") (pin "5") (pinfunction "I0_5") (pintype "input"))
      (node (ref "IC3") (pin "9") (pinfunction "I1_9") (pintype "input"))
      (node (ref "IC4") (pin "4") (pinfunction "A2_4") (pintype "input"))
      (node (ref "IC5") (pin "11") (pinfunction "I0_11") (pintype "input"))
      (node (ref "IC5") (pin "3") (pinfunction "I1_3") (pintype "input"))
      (node (ref "IC5") (pin "5") (pinfunction "I0_5") (pintype "input"))
      (node (ref "IC5") (pin "9") (pinfunction "I1_9") (pintype "input"))
    )
    (net (code "79") (name "SOLFEED") (class "Default")
      (node (ref "C5") (pin "1") (pinfunction "1_1") (pintype "passive"))
      (node (ref "D17") (pin "A") (pinfunction "A_A") (pintype "passive"))
      (node (ref "LSP9") (pin "MP") (pinfunction "MP_MP") (pintype "passive"))
      (node (ref "OK3") (pin "7") (pinfunction "EMIT_7") (pintype "passive"))
      (node (ref "Q9") (pin "3") (pinfunction "E_3") (pintype "passive"))
    )
    (net (code "80") (name "SOLHOLE") (class "Default")
      (node (ref "C6") (pin "1") (pinfunction "1_1") (pintype "passive"))
      (node (ref "D19") (pin "A") (pinfunction "A_A") (pintype "passive"))
      (node (ref "LSP10") (pin "MP") (pinfunction "MP_MP") (pintype "passive"))
      (node (ref "OK3") (pin "5") (pinfunction "EMIT_5") (pintype "passive"))
      (node (ref "Q10") (pin "3") (pinfunction "E_3") (pintype "passive"))
    )
    (net (code "81") (name "SYNC") (class "Default")
      (node (ref "IC2") (pin "3") (pinfunction "Q_3") (pintype "output"))
      (node (ref "IC7") (pin "11") (pinfunction "CLK_11") (pintype "input"))
      (node (ref "SV1") (pin "8") (pinfunction "8_8") (pintype "passive"))
    )
    (net (code "82") (name "VCC") (class "Default")
      (node (ref "IC2") (pin "4") (pinfunction "R_4") (pintype "input"))
      (node (ref "IC2") (pin "8") (pinfunction "V+_8") (pintype "power_in"))
      (node (ref "IC4") (pin "5") (pinfunction "B_5") (pintype "input"))
      (node (ref "IC7") (pin "2") (pinfunction "D_2") (pintype "input"))
      (node (ref "R21") (pin "E") (pinfunction "E_E") (pintype "passive"))
      (node (ref "R21") (pin "S") (pinfunction "S_S") (pintype "passive"))
      (node (ref "R22") (pin "2") (pinfunction "2_2") (pintype "passive"))
      (node (ref "R23") (pin "2") (pinfunction "2_2") (pintype "passive"))
      (node (ref "R24") (pin "E") (pinfunction "E_E") (pintype "passive"))
      (node (ref "R24") (pin "S") (pinfunction "S_S") (pintype "passive"))
      (node (ref "R36") (pin "2") (pinfunction "2_2") (pintype "passive"))
      (node (ref "R37") (pin "2") (pinfunction "2_2") (pintype "passive"))
      (node (ref "R38") (pin "E") (pinfunction "E_E") (pintype "passive"))
      (node (ref "R38") (pin "S") (pinfunction "S_S") (pintype "passive"))
      (node (ref "R39") (pin "2") (pinfunction "2_2") (pintype "passive"))
      (node (ref "R40") (pin "2") (pinfunction "2_2") (pintype "passive"))
      (node (ref "R41") (pin "2") (pinfunction "2_2") (pintype "passive"))
      (node (ref "R42") (pin "2") (pinfunction "2_2") (pintype "passive"))
      (node (ref "R43") (pin "2") (pinfunction "2_2") (pintype "passive"))
      (node (ref "R44") (pin "2") (pinfunction "2_2") (pintype "passive"))
    )
    (net (code "83") (name "unconnected-(IC1A-R-Pad9)") (class "Default")
      (node (ref "IC1") (pin "9") (pinfunction "R_9") (pintype "input"))
    )
    (net (code "84") (name "unconnected-(IC2-CV-Pad5)") (class "Default")
      (node (ref "IC2") (pin "5") (pinfunction "CV_5") (pintype "input"))
    )
    (net (code "85") (name "unconnected-(IC4A-R-Pad9)") (class "Default")
      (node (ref "IC4") (pin "9") (pinfunction "R_9") (pintype "input"))
    )
    (net (code "86") (name "unconnected-(IC7A-Q-Pad5)") (class "Default")
      (node (ref "IC7") (pin "5") (pinfunction "Q_5") (pintype "output"))
    )
    (net (code "87") (name "unconnected-(IC7B-Q-Pad9)") (class "Default")
      (node (ref "IC7") (pin "9") (pinfunction "Q_9") (pintype "output"))
    )
    (net (code "88") (name "unconnected-(SV1-Pad1)") (class "Default")
      (node (ref "SV1") (pin "1") (pinfunction "1_1") (pintype "passive"))
    )
    (net (code "89") (name "unconnected-(SV1-Pad2)") (class "Default")
      (node (ref "SV1") (pin "2") (pinfunction "2_2") (pintype "passive"))
    )
    (net (code "90") (name "unconnected-(SV1-Pad3)") (class "Default")
      (node (ref "SV1") (pin "3") (pinfunction "3_3") (pintype "passive"))
    )
    (net (code "91") (name "unconnected-(SV1-Pad4)") (class "Default")
      (node (ref "SV1") (pin "4") (pinfunction "4_4") (pintype "passive"))
    )
    (net (code "92") (name "unconnected-(SV1-Pad5)") (class "Default")
      (node (ref "SV1") (pin "5") (pinfunction "5_5") (pintype "passive"))
    )
    (net (code "93") (name "unconnected-(SV1-Pad6)") (class "Default")
      (node (ref "SV1") (pin "6") (pinfunction "6_6") (pintype "passive"))
    )
    (net (code "94") (name "unconnected-(SV1-Pad7)") (class "Default")
      (node (ref "SV1") (pin "7") (pinfunction "7_7") (pintype "passive"))
    )
    (net (code "95") (name "unconnected-(SV1-Pad9)") (class "Default")
      (node (ref "SV1") (pin "9") (pinfunction "9_9") (pintype "passive"))
    )
    (net (code "96") (name "unconnected-(SV1-Pad10)") (class "Default")
      (node (ref "SV1") (pin "10") (pinfunction "10_10") (pintype "passive"))
    )
    (net (code "97") (name "unconnected-(SV1-Pad11)") (class "Default")
      (node (ref "SV1") (pin "11") (pinfunction "11_11") (pintype "passive"))
    )
    (net (code "98") (name "unconnected-(SV1-Pad13)") (class "Default")
      (node (ref "SV1") (pin "13") (pinfunction "13_13") (pintype "passive"))
    )
    (net (code "99") (name "unconnected-(SV1-Pad14)") (class "Default")
      (node (ref "SV1") (pin "14") (pinfunction "14_14") (pintype "passive"))
    )
    (net (code "100") (name "unconnected-(SV1-Pad15)") (class "Default")
      (node (ref "SV1") (pin "15") (pinfunction "15_15") (pintype "passive"))
    )
    (net (code "101") (name "unconnected-(SV1-Pad17)") (class "Default")
      (node (ref "SV1") (pin "17") (pinfunction "17_17") (pintype "passive"))
    )
    (net (code "102") (name "unconnected-(SV1-Pad19)") (class "Default")
      (node (ref "SV1") (pin "19") (pinfunction "19_19") (pintype "passive"))
    )
    (net (code "103") (name "unconnected-(SV1-Pad21)") (class "Default")
      (node (ref "SV1") (pin "21") (pinfunction "21_21") (pintype "passive"))
    )
    (net (code "104") (name "unconnected-(SV1-Pad23)") (class "Default")
      (node (ref "SV1") (pin "23") (pinfunction "23_23") (pintype "passive"))
    )
    (net (code "105") (name "unconnected-(SV1-Pad24)") (class "Default")
      (node (ref "SV1") (pin "24") (pinfunction "24_24") (pintype "passive"))
    )
    (net (code "106") (name "unconnected-(SV1-Pad25)") (class "Default")
      (node (ref "SV1") (pin "25") (pinfunction "25_25") (pintype "passive"))
    )
    (net (code "107") (name "unconnected-(SV1-Pad27)") (class "Default")
      (node (ref "SV1") (pin "27") (pinfunction "27_27") (pintype "passive"))
    )
    (net (code "108") (name "unconnected-(SV1-Pad29)") (class "Default")
      (node (ref "SV1") (pin "29") (pinfunction "29_29") (pintype "passive"))
    )
    (net (code "109") (name "unconnected-(SV1-Pad31)") (class "Default")
      (node (ref "SV1") (pin "31") (pinfunction "31_31") (pintype "passive"))
    )
    (net (code "110") (name "unconnected-(SV1-Pad33)") (class "Default")
      (node (ref "SV1") (pin "33") (pinfunction "33_33") (pintype "passive"))
    )
    (net (code "111") (name "unconnected-(SV1-Pad34)") (class "Default")
      (node (ref "SV1") (pin "34") (pinfunction "34_34") (pintype "passive"))
    )
    (net (code "112") (name "unconnected-(SV1-Pad35)") (class "Default")
      (node (ref "SV1") (pin "35") (pinfunction "35_35") (pintype "passive"))
    )
    (net (code "113") (name "unconnected-(SV1-Pad36)") (class "Default")
      (node (ref "SV1") (pin "36") (pinfunction "36_36") (pintype "passive"))
    )
    (net (code "114") (name "unconnected-(SV1-Pad37)") (class "Default")
      (node (ref "SV1") (pin "37") (pinfunction "37_37") (pintype "passive"))
    )
    (net (code "115") (name "unconnected-(SV1-Pad38)") (class "Default")
      (node (ref "SV1") (pin "38") (pinfunction "38_38") (pintype "passive"))
    )
    (net (code "116") (name "unconnected-(SV1-Pad39)") (class "Default")
      (node (ref "SV1") (pin "39") (pinfunction "39_39") (pintype "passive"))
    )
    (net (code "117") (name "unconnected-(SV1-Pad40)") (class "Default")
      (node (ref "SV1") (pin "40") (pinfunction "40_40") (pintype "passive"))
    )
    (net (code "118") (name "~{PUNHOLE}") (class "Default")
      (node (ref "OK3") (pin "4") (pinfunction "C_4") (pintype "passive"))
    )
    (net (code "119") (name "~{RESET}") (class "Default")
      (node (ref "IC7") (pin "13") (pinfunction "CLR_13") (pintype "input"))
      (node (ref "IC7") (pin "4") (pinfunction "PRE_4") (pintype "input"))
    )
    (net (code "120") (name "~{SETBUSY}") (class "Default")
      (node (ref "IC1") (pin "1") (pinfunction "~{Q}_1") (pintype "output"))
      (node (ref "IC7") (pin "1") (pinfunction "CLR_1") (pintype "input"))
      (node (ref "IC7") (pin "10") (pinfunction "PRE_10") (pintype "input"))
    )
  )
)
